# Channel.net
KiCad netlist of a schematic drawn in Altium Designer
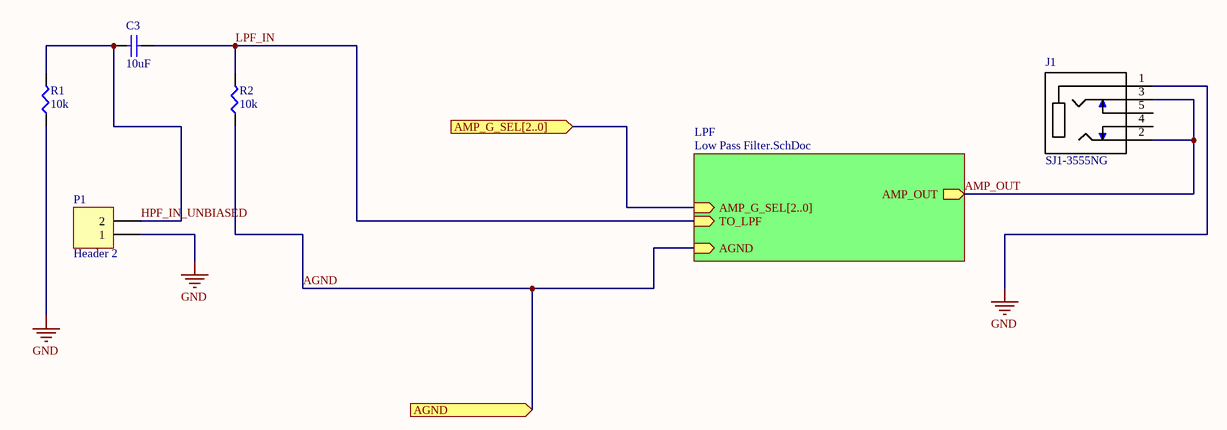
[diagram p0: Channel.SchDoc]

(export (version "E")
  (design (tool "Eeschema 10.0.6"))
  (components
    (comp (ref "C3")
      (value "10uF")
      (footprint "C0805")
      (description "Unpolarized Capacitor")
      (fields (field (name "Comment") "Cap"))
      (libsource (lib "URC_Lib") (part "Cap"))
    )
    (comp (ref "J1")
      (value "SJ1-3555NG")
      (footprint "CUI_SJ1-3555NG")
      (libsource (lib "SJ1-3555NG") (part "SJ1-3555NG"))
    )
    (comp (ref "P1")
      (value "Header 2")
      (footprint "HDR1X2")
      (description "Header, 2-Pin")
      (fields (field (name "PUBLISHER") "Altium Limited"))
      (libsource (lib "Miscellaneous Connectors") (part "Header 2"))
    )
    (comp (ref "R1")
      (value "10k")
      (footprint "SMD-0805-RES")
      (description "RES SMD 10K OHM 1% 1/8W 0805")
      (fields
        (field (name "PART NUMBER") "ERJ-6ENF1002V")
        (field (name "DIGI-KEY PART NUMBER") "P10.0KCCT-ND")
      )
      (libsource (lib "Panasonic_ERJ_0805") (part "ERJ-6ENF1002V"))
    )
    (comp (ref "R2")
      (value "10k")
      (footprint "SMD-0805-RES")
      (description "RES SMD 10K OHM 1% 1/8W 0805")
      (fields
        (field (name "PART NUMBER") "ERJ-6ENF1002V")
        (field (name "DIGI-KEY PART NUMBER") "P10.0KCCT-ND")
      )
      (libsource (lib "Panasonic_ERJ_0805") (part "ERJ-6ENF1002V"))
    )
  )
  (nets
    (net (code "4") (name "/AGND") (class "Default")
      (node (ref "R2") (pin "1") (pinfunction "1_1") (pintype "passive"))
    )
    (net (code "6") (name "/AMP_OUT") (class "Default")
      (node (ref "J1") (pin "2") (pinfunction "2_2") (pintype "passive"))
      (node (ref "J1") (pin "3") (pinfunction "3_3") (pintype "passive"))
    )
    (net (code "7") (name "/HPF_IN_UNBIASED") (class "Default")
      (node (ref "C3") (pin "2") (pinfunction "2_2") (pintype "passive"))
      (node (ref "P1") (pin "2") (pinfunction "2_2") (pintype "passive"))
      (node (ref "R1") (pin "2") (pinfunction "2_2") (pintype "passive"))
    )
    (net (code "8") (name "/LPF_IN") (class "Default")
      (node (ref "C3") (pin "1") (pinfunction "1_1") (pintype "passive"))
      (node (ref "R2") (pin "2") (pinfunction "2_2") (pintype "passive"))
    )
    (net (code "9") (name "GND") (class "Default")
      (node (ref "J1") (pin "1") (pinfunction "1_1") (pintype "passive"))
      (node (ref "P1") (pin "1") (pinfunction "1_1") (pintype "passive"))
      (node (ref "R1") (pin "1") (pinfunction "1_1") (pintype "passive"))
    )
    (net (code "10") (name "unconnected-(J1-Pad4)") (class "Default")
      (node (ref "J1") (pin "4") (pinfunction "4_4") (pintype "passive"))
    )
    (net (code "11") (name "unconnected-(J1-Pad5)") (class "Default")
      (node (ref "J1") (pin "5") (pinfunction "5_5") (pintype "passive"))
    )
  )
)
